# 1_41.net
KiCad netlist of a schematic drawn in EasyEDA Pro
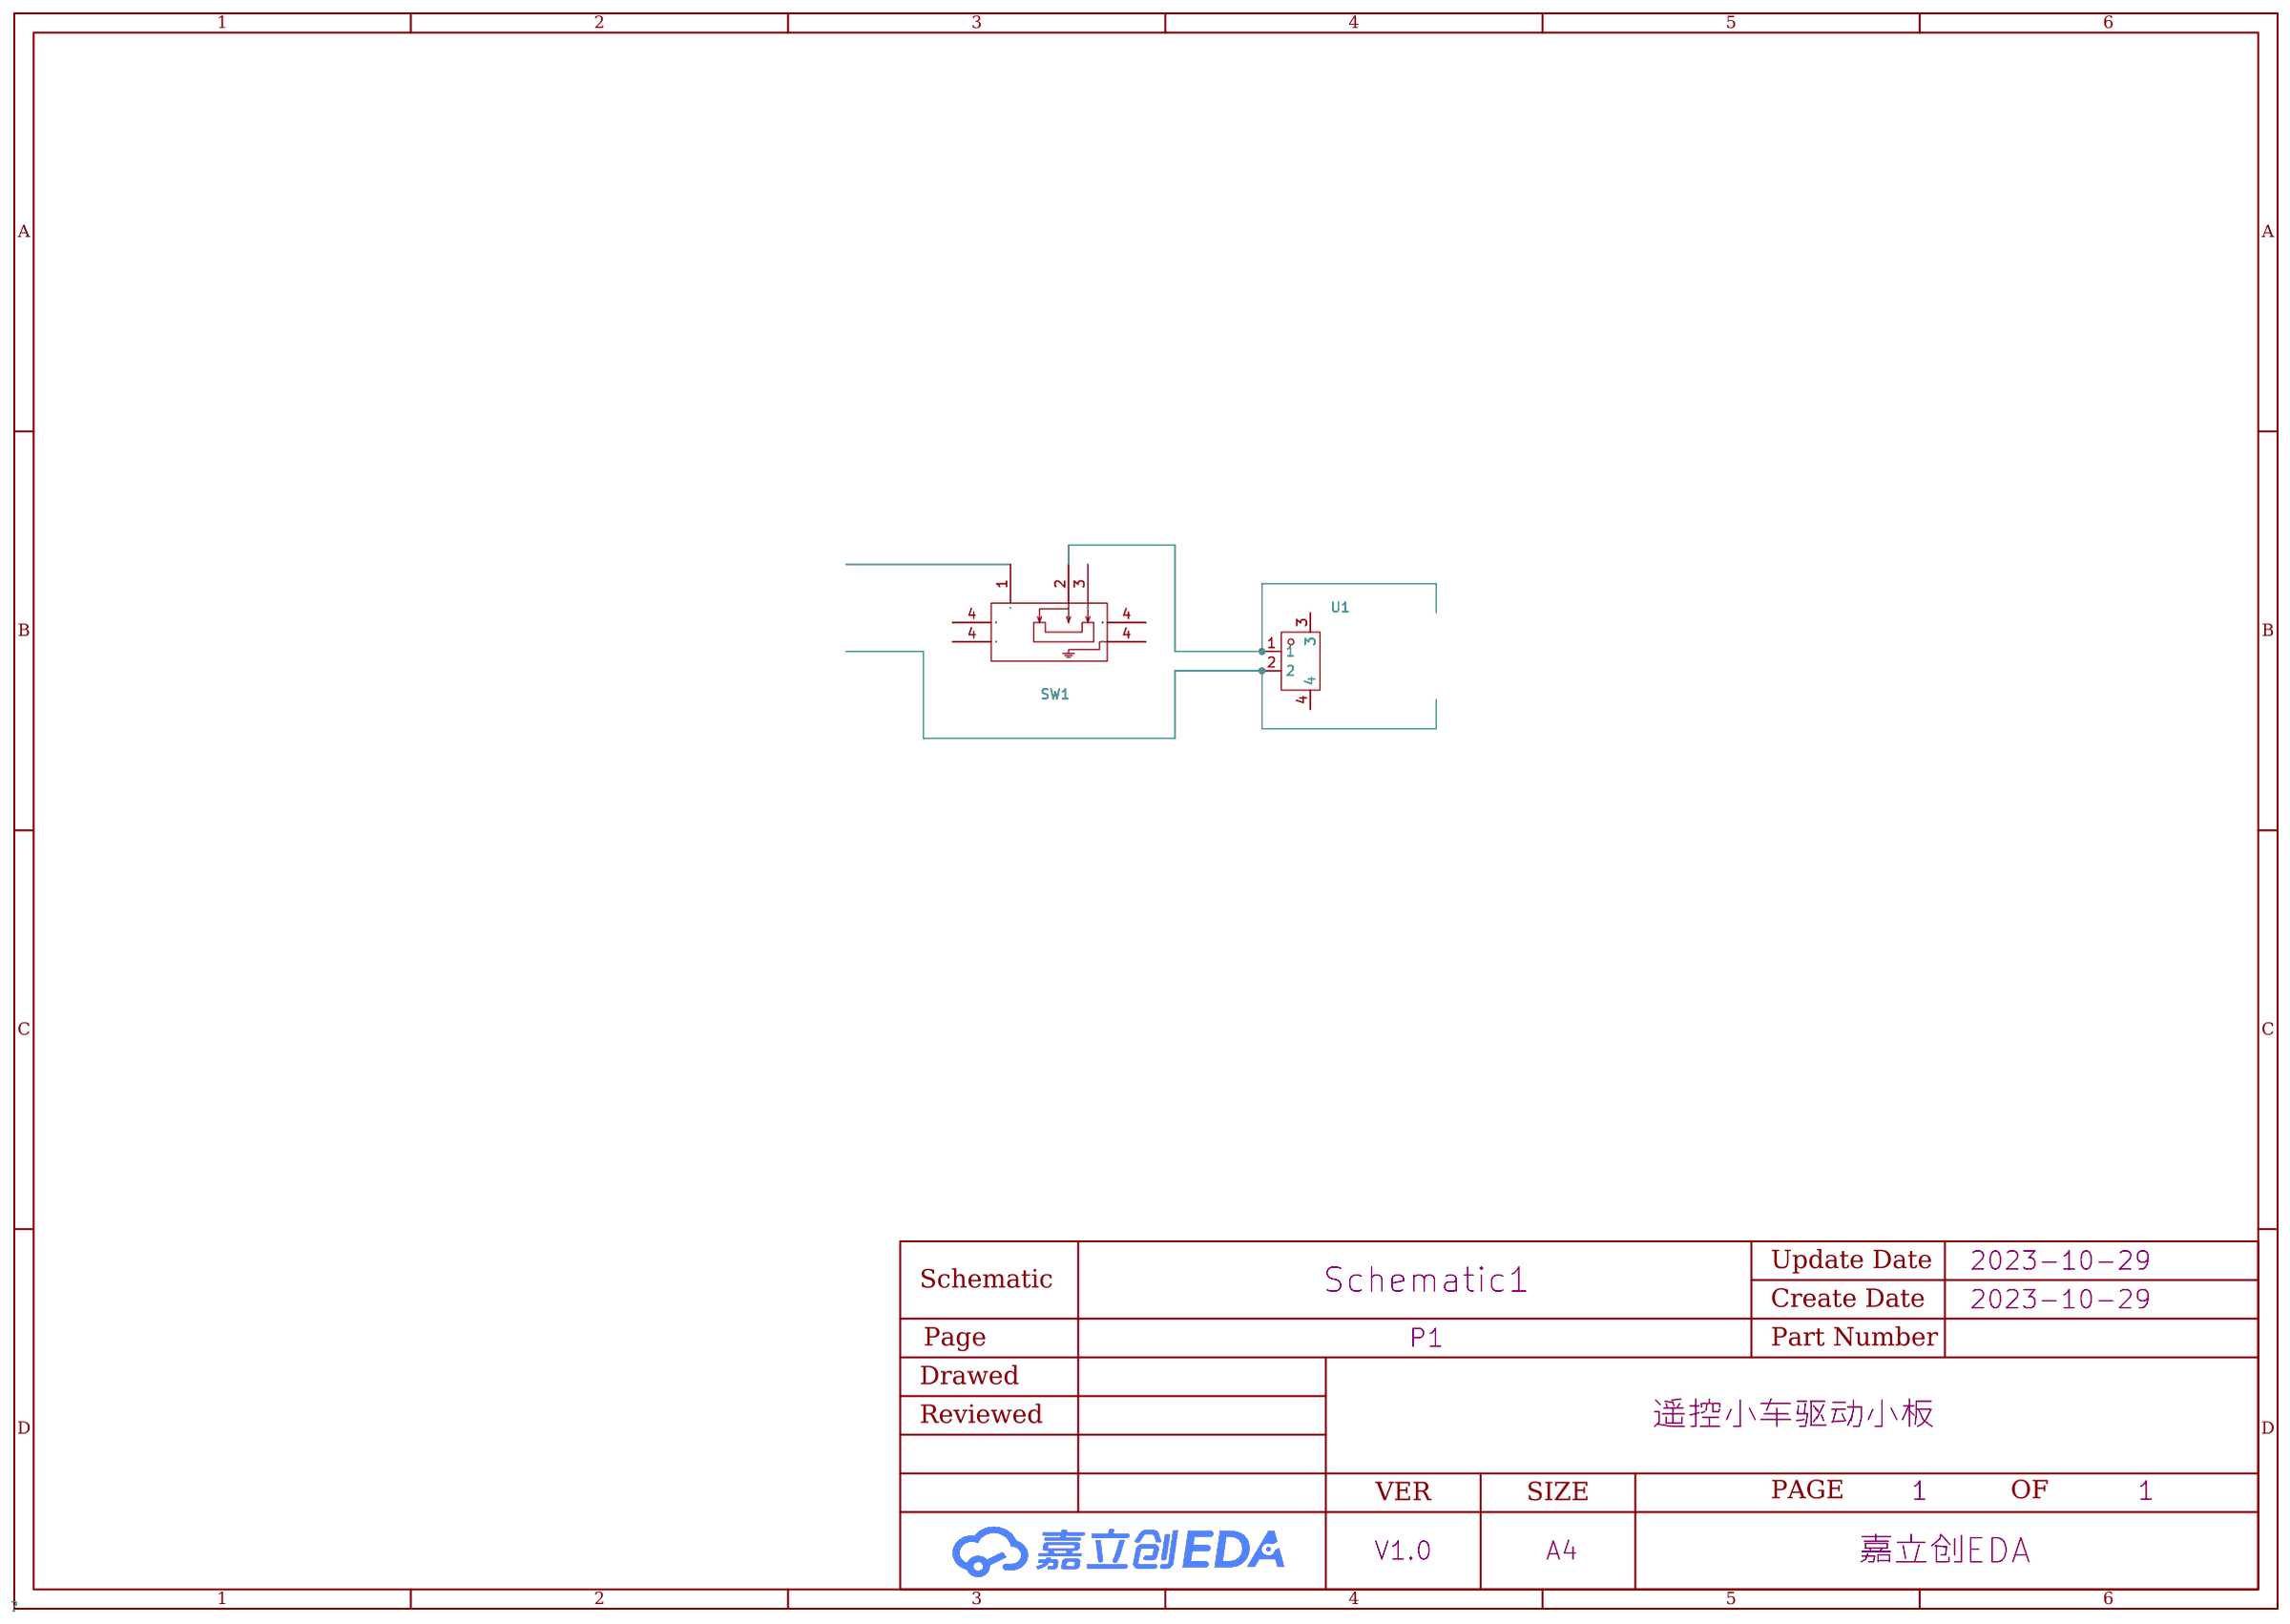
[diagram p0: schematic sheet]

(export (version "E")
  (design (tool "Eeschema 10.0.6"))
  (components
    (comp (ref "SW1")
      (value "MSK12C02")
      (footprint "easyedapro:SW-TH_MSK12C02")
      (fields (field (name "Manufacturer") "SHOU HAN(首韩)"))
      (libsource (lib "easyedapro") (part "MSK12C02"))
    )
    (comp (ref "U1")
      (value "XD-GH-2PWT")
      (footprint "easyedapro:CONN-SMD_GH-2PWT")
      (description "参考系列:GH;间距:1.25mm;插针结构:1x2P;排数:1;每排PIN数:2;公母:公型插针;安装方式:卧贴;额定电流:1A;触头镀层:锡;工作温度范围:-40°C~+105°C;")
      (fields (field (name "Manufacturer") "XUNDA(讯答)"))
      (libsource (lib "easyedapro") (part "XD-GH-2PWT"))
    )
  )
  (nets
    (net (code "1") (name "Net-(SW1-Pad2)") (class "Default")
      (node (ref "SW1") (pin "2") (pinfunction "2_2") (pintype "input"))
      (node (ref "U1") (pin "1") (pinfunction "1_1") (pintype "unspecified"))
    )
    (net (code "2") (name "unconnected-(SW1-Pad1)") (class "Default")
      (node (ref "SW1") (pin "1") (pinfunction "1_1") (pintype "input"))
    )
    (net (code "3") (name "unconnected-(SW1-Pad3)") (class "Default")
      (node (ref "SW1") (pin "3") (pinfunction "3_3") (pintype "input"))
    )
    (net (code "4") (name "unconnected-(SW1-Pad4)") (class "Default")
      (node (ref "SW1") (pin "4") (pinfunction "4_4") (pintype "input"))
    )
    (net (code "5") (name "unconnected-(SW1-Pad4)_1") (class "Default")
      (node (ref "SW1") (pin "4") (pinfunction "4_4") (pintype "input"))
    )
    (net (code "6") (name "unconnected-(SW1-Pad4)_2") (class "Default")
      (node (ref "SW1") (pin "4") (pinfunction "4_4") (pintype "input"))
    )
    (net (code "7") (name "unconnected-(SW1-Pad4)_3") (class "Default")
      (node (ref "SW1") (pin "4") (pinfunction "4_4") (pintype "input"))
    )
    (net (code "8") (name "unconnected-(U1-Pad2)") (class "Default")
      (node (ref "U1") (pin "2") (pinfunction "2_2") (pintype "unspecified"))
    )
    (net (code "9") (name "unconnected-(U1-Pad3)") (class "Default")
      (node (ref "U1") (pin "3") (pinfunction "3_3") (pintype "unspecified"))
    )
    (net (code "10") (name "unconnected-(U1-Pad4)") (class "Default")
      (node (ref "U1") (pin "4") (pinfunction "4_4") (pintype "unspecified"))
    )
  )
)
